# CustomArduino.net
KiCad netlist of a schematic drawn in EAGLE
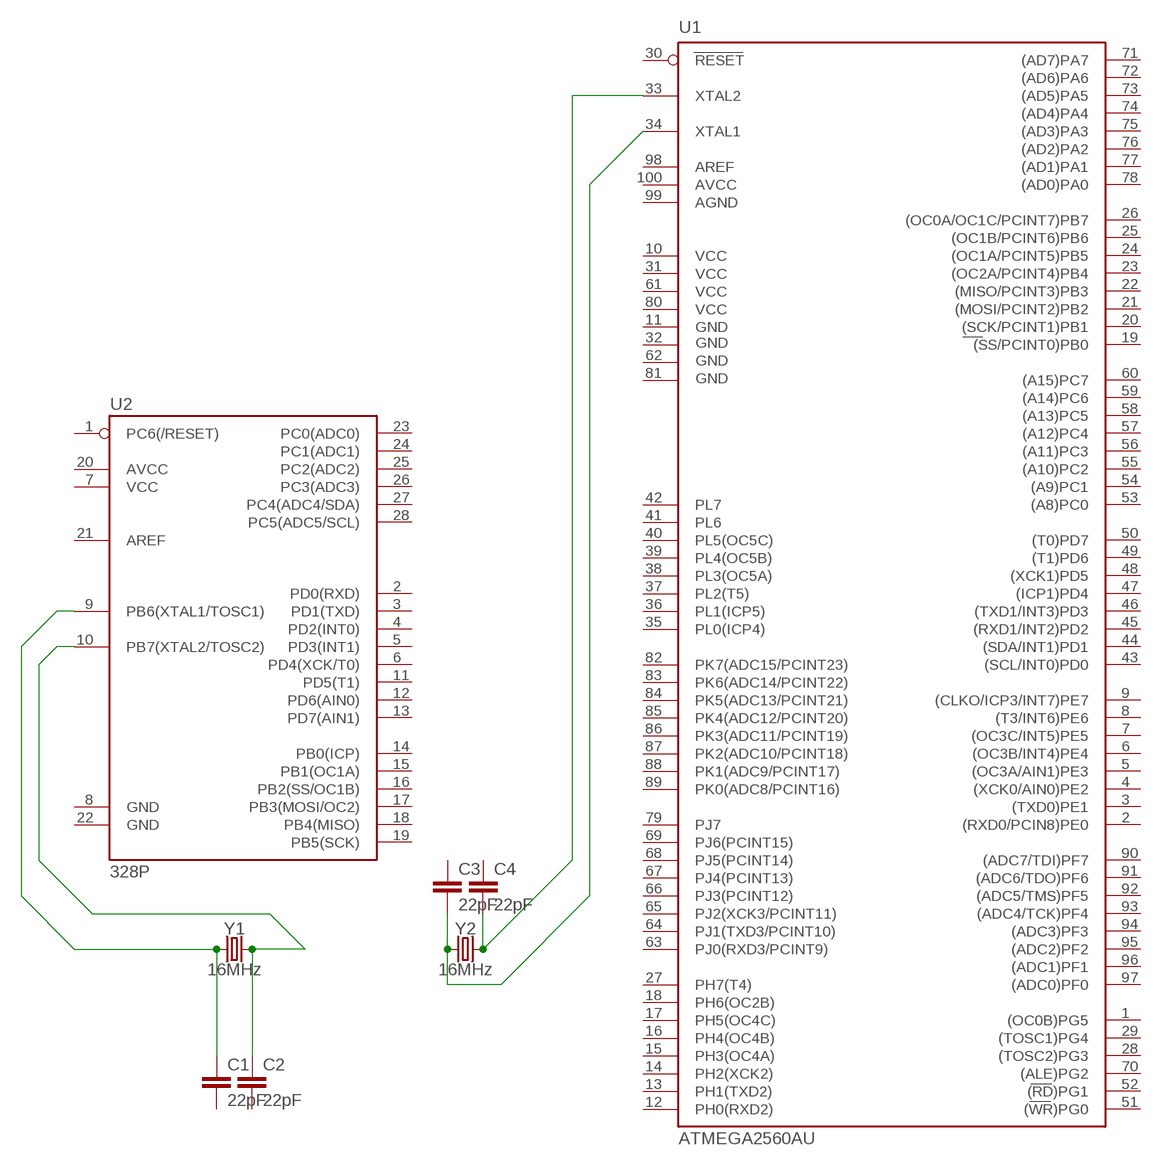
[diagram p0: schematic, sheet 1]

(export (version "E")
  (design (tool "Eeschema 10.0.6"))
  (components
    (comp (ref "C1")
      (value "22pF")
      (footprint "eagle-import:0603")
      (libsource (lib "eagle-import") (part "22PF-0603-50V-5%"))
    )
    (comp (ref "C2")
      (value "22pF")
      (footprint "eagle-import:0603")
      (libsource (lib "eagle-import") (part "22PF-0603-50V-5%"))
    )
    (comp (ref "C3")
      (value "22pF")
      (footprint "eagle-import:0603")
      (libsource (lib "eagle-import") (part "22PF-0603-50V-5%"))
    )
    (comp (ref "C4")
      (value "22pF")
      (footprint "eagle-import:0603")
      (libsource (lib "eagle-import") (part "22PF-0603-50V-5%"))
    )
    (comp (ref "U1")
      (value "ATMEGA2560AU")
      (footprint "eagle-import:TQFP100")
      (libsource (lib "eagle-import") (part "ATMEGA2560AU"))
    )
    (comp (ref "U2")
      (value "328P")
      (footprint "eagle-import:DIP28")
      (libsource (lib "eagle-import") (part "ATMEGA328P_PDIP"))
    )
    (comp (ref "Y1")
      (value "16MHz")
      (footprint "eagle-import:CRYSTAL-SMD-5X3.2-4PAD")
      (libsource (lib "eagle-import") (part "CRYSTAL-16MHZSMD-5X3.2"))
    )
    (comp (ref "Y2")
      (value "16MHz")
      (footprint "eagle-import:CRYSTAL-SMD-5X3.2-4PAD")
      (libsource (lib "eagle-import") (part "CRYSTAL-16MHZSMD-5X3.2"))
    )
  )
  (nets
    (net (code "1") (name "/AGND") (class "Default")
      (node (ref "U1") (pin "99") (pinfunction "AGND_99") (pintype "power_in"))
    )
    (net (code "2") (name "/AVCC") (class "Default")
      (node (ref "U1") (pin "100") (pinfunction "AVCC_100") (pintype "power_in"))
    )
    (net (code "3") (name "/GND") (class "Default")
      (node (ref "U1") (pin "11") (pinfunction "GND_11") (pintype "power_in"))
    )
    (net (code "4") (name "/GND1") (class "Default")
      (node (ref "U1") (pin "32") (pinfunction "GND1_32") (pintype "power_in"))
    )
    (net (code "5") (name "/GND2") (class "Default")
      (node (ref "U1") (pin "62") (pinfunction "GND2_62") (pintype "power_in"))
    )
    (net (code "6") (name "/GND3") (class "Default")
      (node (ref "U1") (pin "81") (pinfunction "GND3_81") (pintype "power_in"))
    )
    (net (code "7") (name "/VCC") (class "Default")
      (node (ref "U1") (pin "10") (pinfunction "VCC_10") (pintype "power_in"))
    )
    (net (code "8") (name "/VCC1") (class "Default")
      (node (ref "U1") (pin "31") (pinfunction "VCC1_31") (pintype "power_in"))
    )
    (net (code "9") (name "/VCC2") (class "Default")
      (node (ref "U1") (pin "61") (pinfunction "VCC2_61") (pintype "power_in"))
    )
    (net (code "10") (name "/VCC3") (class "Default")
      (node (ref "U1") (pin "80") (pinfunction "VCC3_80") (pintype "power_in"))
    )
    (net (code "11") (name "Net-(U1-XTAL1)") (class "Default")
      (node (ref "C3") (pin "2") (pinfunction "2_2") (pintype "passive"))
      (node (ref "U1") (pin "34") (pinfunction "XTAL1_34") (pintype "input"))
      (node (ref "Y2") (pin "1") (pinfunction "1_1") (pintype "passive"))
    )
    (net (code "12") (name "Net-(U1-XTAL2)") (class "Default")
      (node (ref "C4") (pin "2") (pinfunction "2_2") (pintype "passive"))
      (node (ref "U1") (pin "33") (pinfunction "XTAL2_33") (pintype "output"))
      (node (ref "Y2") (pin "3") (pinfunction "2_3") (pintype "passive"))
    )
    (net (code "13") (name "Net-(U2-PB6(XTAL1{slash}TOSC1))") (class "Default")
      (node (ref "C1") (pin "1") (pinfunction "1_1") (pintype "passive"))
      (node (ref "U2") (pin "9") (pinfunction "PB6(XTAL1/TOSC1)_9") (pintype "bidirectional"))
      (node (ref "Y1") (pin "1") (pinfunction "1_1") (pintype "passive"))
    )
    (net (code "14") (name "Net-(U2-PB7(XTAL2{slash}TOSC2))") (class "Default")
      (node (ref "C2") (pin "1") (pinfunction "1_1") (pintype "passive"))
      (node (ref "U2") (pin "10") (pinfunction "PB7(XTAL2/TOSC2)_10") (pintype "bidirectional"))
      (node (ref "Y1") (pin "3") (pinfunction "2_3") (pintype "passive"))
    )
    (net (code "15") (name "unconnected-(C1-Pad2)") (class "Default")
      (node (ref "C1") (pin "2") (pinfunction "2_2") (pintype "passive"))
    )
    (net (code "16") (name "unconnected-(C2-Pad2)") (class "Default")
      (node (ref "C2") (pin "2") (pinfunction "2_2") (pintype "passive"))
    )
    (net (code "17") (name "unconnected-(C3-Pad1)") (class "Default")
      (node (ref "C3") (pin "1") (pinfunction "1_1") (pintype "passive"))
    )
    (net (code "18") (name "unconnected-(C4-Pad1)") (class "Default")
      (node (ref "C4") (pin "1") (pinfunction "1_1") (pintype "passive"))
    )
    (net (code "19") (name "unconnected-(U1-(A8)PC0-Pad53)") (class "Default")
      (node (ref "U1") (pin "53") (pinfunction "(A8)PC0_53") (pintype "bidirectional"))
    )
    (net (code "20") (name "unconnected-(U1-(A9)PC1-Pad54)") (class "Default")
      (node (ref "U1") (pin "54") (pinfunction "(A9)PC1_54") (pintype "bidirectional"))
    )
    (net (code "21") (name "unconnected-(U1-(A10)PC2-Pad55)") (class "Default")
      (node (ref "U1") (pin "55") (pinfunction "(A10)PC2_55") (pintype "bidirectional"))
    )
    (net (code "22") (name "unconnected-(U1-(A11)PC3-Pad56)") (class "Default")
      (node (ref "U1") (pin "56") (pinfunction "(A11)PC3_56") (pintype "bidirectional"))
    )
    (net (code "23") (name "unconnected-(U1-(A12)PC4-Pad57)") (class "Default")
      (node (ref "U1") (pin "57") (pinfunction "(A12)PC4_57") (pintype "bidirectional"))
    )
    (net (code "24") (name "unconnected-(U1-(A13)PC5-Pad58)") (class "Default")
      (node (ref "U1") (pin "58") (pinfunction "(A13)PC5_58") (pintype "bidirectional"))
    )
    (net (code "25") (name "unconnected-(U1-(A14)PC6-Pad59)") (class "Default")
      (node (ref "U1") (pin "59") (pinfunction "(A14)PC6_59") (pintype "bidirectional"))
    )
    (net (code "26") (name "unconnected-(U1-(A15)PC7-Pad60)") (class "Default")
      (node (ref "U1") (pin "60") (pinfunction "(A15)PC7_60") (pintype "bidirectional"))
    )
    (net (code "27") (name "unconnected-(U1-(AD0)PA0-Pad78)") (class "Default")
      (node (ref "U1") (pin "78") (pinfunction "(AD0)PA0_78") (pintype "bidirectional"))
    )
    (net (code "28") (name "unconnected-(U1-(AD1)PA1-Pad77)") (class "Default")
      (node (ref "U1") (pin "77") (pinfunction "(AD1)PA1_77") (pintype "bidirectional"))
    )
    (net (code "29") (name "unconnected-(U1-(AD2)PA2-Pad76)") (class "Default")
      (node (ref "U1") (pin "76") (pinfunction "(AD2)PA2_76") (pintype "bidirectional"))
    )
    (net (code "30") (name "unconnected-(U1-(AD3)PA3-Pad75)") (class "Default")
      (node (ref "U1") (pin "75") (pinfunction "(AD3)PA3_75") (pintype "bidirectional"))
    )
    (net (code "31") (name "unconnected-(U1-(AD4)PA4-Pad74)") (class "Default")
      (node (ref "U1") (pin "74") (pinfunction "(AD4)PA4_74") (pintype "bidirectional"))
    )
    (net (code "32") (name "unconnected-(U1-(AD5)PA5-Pad73)") (class "Default")
      (node (ref "U1") (pin "73") (pinfunction "(AD5)PA5_73") (pintype "bidirectional"))
    )
    (net (code "33") (name "unconnected-(U1-(AD6)PA6-Pad72)") (class "Default")
      (node (ref "U1") (pin "72") (pinfunction "(AD6)PA6_72") (pintype "bidirectional"))
    )
    (net (code "34") (name "unconnected-(U1-(AD7)PA7-Pad71)") (class "Default")
      (node (ref "U1") (pin "71") (pinfunction "(AD7)PA7_71") (pintype "bidirectional"))
    )
    (net (code "35") (name "unconnected-(U1-(ADC0)PF0-Pad97)") (class "Default")
      (node (ref "U1") (pin "97") (pinfunction "(ADC0)PF0_97") (pintype "bidirectional"))
    )
    (net (code "36") (name "unconnected-(U1-(ADC1)PF1-Pad96)") (class "Default")
      (node (ref "U1") (pin "96") (pinfunction "(ADC1)PF1_96") (pintype "bidirectional"))
    )
    (net (code "37") (name "unconnected-(U1-(ADC2)PF2-Pad95)") (class "Default")
      (node (ref "U1") (pin "95") (pinfunction "(ADC2)PF2_95") (pintype "bidirectional"))
    )
    (net (code "38") (name "unconnected-(U1-(ADC3)PF3-Pad94)") (class "Default")
      (node (ref "U1") (pin "94") (pinfunction "(ADC3)PF3_94") (pintype "bidirectional"))
    )
    (net (code "39") (name "unconnected-(U1-(ADC4{slash}TCK)PF4-Pad93)") (class "Default")
      (node (ref "U1") (pin "93") (pinfunction "(ADC4/TCK)PF4_93") (pintype "bidirectional"))
    )
    (net (code "40") (name "unconnected-(U1-(ADC5{slash}TMS)PF5-Pad92)") (class "Default")
      (node (ref "U1") (pin "92") (pinfunction "(ADC5/TMS)PF5_92") (pintype "bidirectional"))
    )
    (net (code "41") (name "unconnected-(U1-(ADC6{slash}TDO)PF6-Pad91)") (class "Default")
      (node (ref "U1") (pin "91") (pinfunction "(ADC6/TDO)PF6_91") (pintype "bidirectional"))
    )
    (net (code "42") (name "unconnected-(U1-(ADC7{slash}TDI)PF7-Pad90)") (class "Default")
      (node (ref "U1") (pin "90") (pinfunction "(ADC7/TDI)PF7_90") (pintype "bidirectional"))
    )
    (net (code "43") (name "unconnected-(U1-(ALE)PG2-Pad70)") (class "Default")
      (node (ref "U1") (pin "70") (pinfunction "(ALE)PG2_70") (pintype "bidirectional"))
    )
    (net (code "44") (name "unconnected-(U1-(CLKO{slash}ICP3{slash}INT7)PE7-Pad9)") (class "Default")
      (node (ref "U1") (pin "9") (pinfunction "(CLKO/ICP3/INT7)PE7_9") (pintype "bidirectional"))
    )
    (net (code "45") (name "unconnected-(U1-(ICP1)PD4-Pad47)") (class "Default")
      (node (ref "U1") (pin "47") (pinfunction "(ICP1)PD4_47") (pintype "bidirectional"))
    )
    (net (code "46") (name "unconnected-(U1-(MISO{slash}PCINT3)PB3-Pad22)") (class "Default")
      (node (ref "U1") (pin "22") (pinfunction "(MISO/PCINT3)PB3_22") (pintype "bidirectional"))
    )
    (net (code "47") (name "unconnected-(U1-(MOSI{slash}PCINT2)PB2-Pad21)") (class "Default")
      (node (ref "U1") (pin "21") (pinfunction "(MOSI/PCINT2)PB2_21") (pintype "bidirectional"))
    )
    (net (code "48") (name "unconnected-(U1-(OC0A{slash}OC1C{slash}PCINT7)PB7-Pad26)") (class "Default")
      (node (ref "U1") (pin "26") (pinfunction "(OC0A/OC1C/PCINT7)PB7_26") (pintype "bidirectional"))
    )
    (net (code "49") (name "unconnected-(U1-(OC0B)PG5-Pad1)") (class "Default")
      (node (ref "U1") (pin "1") (pinfunction "(OC0B)PG5_1") (pintype "bidirectional"))
    )
    (net (code "50") (name "unconnected-(U1-(OC1A{slash}PCINT5)PB5-Pad24)") (class "Default")
      (node (ref "U1") (pin "24") (pinfunction "(OC1A/PCINT5)PB5_24") (pintype "bidirectional"))
    )
    (net (code "51") (name "unconnected-(U1-(OC1B{slash}PCINT6)PB6-Pad25)") (class "Default")
      (node (ref "U1") (pin "25") (pinfunction "(OC1B/PCINT6)PB6_25") (pintype "bidirectional"))
    )
    (net (code "52") (name "unconnected-(U1-(OC2A{slash}PCINT4)PB4-Pad23)") (class "Default")
      (node (ref "U1") (pin "23") (pinfunction "(OC2A/PCINT4)PB4_23") (pintype "bidirectional"))
    )
    (net (code "53") (name "unconnected-(U1-(OC3A{slash}AIN1)PE3-Pad5)") (class "Default")
      (node (ref "U1") (pin "5") (pinfunction "(OC3A/AIN1)PE3_5") (pintype "bidirectional"))
    )
    (net (code "54") (name "unconnected-(U1-(OC3B{slash}INT4)PE4-Pad6)") (class "Default")
      (node (ref "U1") (pin "6") (pinfunction "(OC3B/INT4)PE4_6") (pintype "bidirectional"))
    )
    (net (code "55") (name "unconnected-(U1-(OC3C{slash}INT5)PE5-Pad7)") (class "Default")
      (node (ref "U1") (pin "7") (pinfunction "(OC3C/INT5)PE5_7") (pintype "bidirectional"))
    )
    (net (code "56") (name "unconnected-(U1-(RD)PG1-Pad52)") (class "Default")
      (node (ref "U1") (pin "52") (pinfunction "(RD)PG1_52") (pintype "bidirectional"))
    )
    (net (code "57") (name "unconnected-(U1-(RXD0{slash}PCIN8)PE0-Pad2)") (class "Default")
      (node (ref "U1") (pin "2") (pinfunction "(RXD0/PCIN8)PE0_2") (pintype "bidirectional"))
    )
    (net (code "58") (name "unconnected-(U1-(RXD1{slash}INT2)PD2-Pad45)") (class "Default")
      (node (ref "U1") (pin "45") (pinfunction "(RXD1/INT2)PD2_45") (pintype "bidirectional"))
    )
    (net (code "59") (name "unconnected-(U1-(SCK{slash}PCINT1)PB1-Pad20)") (class "Default")
      (node (ref "U1") (pin "20") (pinfunction "(SCK/PCINT1)PB1_20") (pintype "bidirectional"))
    )
    (net (code "60") (name "unconnected-(U1-(SCL{slash}INT0)PD0-Pad43)") (class "Default")
      (node (ref "U1") (pin "43") (pinfunction "(SCL/INT0)PD0_43") (pintype "bidirectional"))
    )
    (net (code "61") (name "unconnected-(U1-(SDA{slash}INT1)PD1-Pad44)") (class "Default")
      (node (ref "U1") (pin "44") (pinfunction "(SDA/INT1)PD1_44") (pintype "bidirectional"))
    )
    (net (code "62") (name "unconnected-(U1-(SS{slash}PCINT0)PB0-Pad19)") (class "Default")
      (node (ref "U1") (pin "19") (pinfunction "(SS/PCINT0)PB0_19") (pintype "bidirectional"))
    )
    (net (code "63") (name "unconnected-(U1-(T0)PD7-Pad50)") (class "Default")
      (node (ref "U1") (pin "50") (pinfunction "(T0)PD7_50") (pintype "bidirectional"))
    )
    (net (code "64") (name "unconnected-(U1-(T1)PD6-Pad49)") (class "Default")
      (node (ref "U1") (pin "49") (pinfunction "(T1)PD6_49") (pintype "bidirectional"))
    )
    (net (code "65") (name "unconnected-(U1-(T3{slash}INT6)PE6-Pad8)") (class "Default")
      (node (ref "U1") (pin "8") (pinfunction "(T3/INT6)PE6_8") (pintype "bidirectional"))
    )
    (net (code "66") (name "unconnected-(U1-(TOSC1)PG4-Pad29)") (class "Default")
      (node (ref "U1") (pin "29") (pinfunction "(TOSC1)PG4_29") (pintype "bidirectional"))
    )
    (net (code "67") (name "unconnected-(U1-(TOSC2)PG3-Pad28)") (class "Default")
      (node (ref "U1") (pin "28") (pinfunction "(TOSC2)PG3_28") (pintype "bidirectional"))
    )
    (net (code "68") (name "unconnected-(U1-(TXD0)PE1-Pad3)") (class "Default")
      (node (ref "U1") (pin "3") (pinfunction "(TXD0)PE1_3") (pintype "bidirectional"))
    )
    (net (code "69") (name "unconnected-(U1-(TXD1{slash}INT3)PD3-Pad46)") (class "Default")
      (node (ref "U1") (pin "46") (pinfunction "(TXD1/INT3)PD3_46") (pintype "bidirectional"))
    )
    (net (code "70") (name "unconnected-(U1-(WR)PG0-Pad51)") (class "Default")
      (node (ref "U1") (pin "51") (pinfunction "(WR)PG0_51") (pintype "bidirectional"))
    )
    (net (code "71") (name "unconnected-(U1-(XCK0{slash}AIN0)PE2-Pad4)") (class "Default")
      (node (ref "U1") (pin "4") (pinfunction "(XCK0/AIN0)PE2_4") (pintype "bidirectional"))
    )
    (net (code "72") (name "unconnected-(U1-(XCK1)PD5-Pad48)") (class "Default")
      (node (ref "U1") (pin "48") (pinfunction "(XCK1)PD5_48") (pintype "bidirectional"))
    )
    (net (code "73") (name "unconnected-(U1-AREF-Pad98)") (class "Default")
      (node (ref "U1") (pin "98") (pinfunction "AREF_98") (pintype "bidirectional"))
    )
    (net (code "74") (name "unconnected-(U1-PH0(RXD2)-Pad12)") (class "Default")
      (node (ref "U1") (pin "12") (pinfunction "PH0(RXD2)_12") (pintype "bidirectional"))
    )
    (net (code "75") (name "unconnected-(U1-PH1(TXD2)-Pad13)") (class "Default")
      (node (ref "U1") (pin "13") (pinfunction "PH1(TXD2)_13") (pintype "bidirectional"))
    )
    (net (code "76") (name "unconnected-(U1-PH2(XCK2)-Pad14)") (class "Default")
      (node (ref "U1") (pin "14") (pinfunction "PH2(XCK2)_14") (pintype "bidirectional"))
    )
    (net (code "77") (name "unconnected-(U1-PH3(OC4A)-Pad15)") (class "Default")
      (node (ref "U1") (pin "15") (pinfunction "PH3(OC4A)_15") (pintype "bidirectional"))
    )
    (net (code "78") (name "unconnected-(U1-PH4(OC4B)-Pad16)") (class "Default")
      (node (ref "U1") (pin "16") (pinfunction "PH4(OC4B)_16") (pintype "bidirectional"))
    )
    (net (code "79") (name "unconnected-(U1-PH5(OC4C)-Pad17)") (class "Default")
      (node (ref "U1") (pin "17") (pinfunction "PH5(OC4C)_17") (pintype "bidirectional"))
    )
    (net (code "80") (name "unconnected-(U1-PH6(OC2B)-Pad18)") (class "Default")
      (node (ref "U1") (pin "18") (pinfunction "PH6(OC2B)_18") (pintype "bidirectional"))
    )
    (net (code "81") (name "unconnected-(U1-PH7(T4)-Pad27)") (class "Default")
      (node (ref "U1") (pin "27") (pinfunction "PH7(T4)_27") (pintype "bidirectional"))
    )
    (net (code "82") (name "unconnected-(U1-PJ0(RXD3{slash}PCINT9)-Pad63)") (class "Default")
      (node (ref "U1") (pin "63") (pinfunction "PJ0(RXD3/PCINT9)_63") (pintype "bidirectional"))
    )
    (net (code "83") (name "unconnected-(U1-PJ1(TXD3{slash}PCINT10)-Pad64)") (class "Default")
      (node (ref "U1") (pin "64") (pinfunction "PJ1(TXD3/PCINT10)_64") (pintype "bidirectional"))
    )
    (net (code "84") (name "unconnected-(U1-PJ2(XCK3{slash}PCINT11)-Pad65)") (class "Default")
      (node (ref "U1") (pin "65") (pinfunction "PJ2(XCK3/PCINT11)_65") (pintype "bidirectional"))
    )
    (net (code "85") (name "unconnected-(U1-PJ3(PCINT12)-Pad66)") (class "Default")
      (node (ref "U1") (pin "66") (pinfunction "PJ3(PCINT12)_66") (pintype "bidirectional"))
    )
    (net (code "86") (name "unconnected-(U1-PJ4(PCINT13)-Pad67)") (class "Default")
      (node (ref "U1") (pin "67") (pinfunction "PJ4(PCINT13)_67") (pintype "bidirectional"))
    )
    (net (code "87") (name "unconnected-(U1-PJ5(PCINT14)-Pad68)") (class "Default")
      (node (ref "U1") (pin "68") (pinfunction "PJ5(PCINT14)_68") (pintype "bidirectional"))
    )
    (net (code "88") (name "unconnected-(U1-PJ6(PCINT15)-Pad69)") (class "Default")
      (node (ref "U1") (pin "69") (pinfunction "PJ6(PCINT15)_69") (pintype "bidirectional"))
    )
    (net (code "89") (name "unconnected-(U1-PJ7-Pad79)") (class "Default")
      (node (ref "U1") (pin "79") (pinfunction "PJ7_79") (pintype "bidirectional"))
    )
    (net (code "90") (name "unconnected-(U1-PK0(ADC8{slash}PCINT16)-Pad89)") (class "Default")
      (node (ref "U1") (pin "89") (pinfunction "PK0(ADC8/PCINT16)_89") (pintype "bidirectional"))
    )
    (net (code "91") (name "unconnected-(U1-PK1(ADC9{slash}PCINT17)-Pad88)") (class "Default")
      (node (ref "U1") (pin "88") (pinfunction "PK1(ADC9/PCINT17)_88") (pintype "bidirectional"))
    )
    (net (code "92") (name "unconnected-(U1-PK2(ADC10{slash}PCINT18)-Pad87)") (class "Default")
      (node (ref "U1") (pin "87") (pinfunction "PK2(ADC10/PCINT18)_87") (pintype "bidirectional"))
    )
    (net (code "93") (name "unconnected-(U1-PK3(ADC11{slash}PCINT19)-Pad86)") (class "Default")
      (node (ref "U1") (pin "86") (pinfunction "PK3(ADC11/PCINT19)_86") (pintype "bidirectional"))
    )
    (net (code "94") (name "unconnected-(U1-PK4(ADC12{slash}PCINT20)-Pad85)") (class "Default")
      (node (ref "U1") (pin "85") (pinfunction "PK4(ADC12/PCINT20)_85") (pintype "bidirectional"))
    )
    (net (code "95") (name "unconnected-(U1-PK5(ADC13{slash}PCINT21)-Pad84)") (class "Default")
      (node (ref "U1") (pin "84") (pinfunction "PK5(ADC13/PCINT21)_84") (pintype "bidirectional"))
    )
    (net (code "96") (name "unconnected-(U1-PK6(ADC14{slash}PCINT22)-Pad83)") (class "Default")
      (node (ref "U1") (pin "83") (pinfunction "PK6(ADC14/PCINT22)_83") (pintype "bidirectional"))
    )
    (net (code "97") (name "unconnected-(U1-PK7(ADC15{slash}PCINT23)-Pad82)") (class "Default")
      (node (ref "U1") (pin "82") (pinfunction "PK7(ADC15/PCINT23)_82") (pintype "bidirectional"))
    )
    (net (code "98") (name "unconnected-(U1-PL0(ICP4)-Pad35)") (class "Default")
      (node (ref "U1") (pin "35") (pinfunction "PL0(ICP4)_35") (pintype "bidirectional"))
    )
    (net (code "99") (name "unconnected-(U1-PL1(ICP5)-Pad36)") (class "Default")
      (node (ref "U1") (pin "36") (pinfunction "PL1(ICP5)_36") (pintype "bidirectional"))
    )
    (net (code "100") (name "unconnected-(U1-PL2(T5)-Pad37)") (class "Default")
      (node (ref "U1") (pin "37") (pinfunction "PL2(T5)_37") (pintype "bidirectional"))
    )
    (net (code "101") (name "unconnected-(U1-PL3(OC5A)-Pad38)") (class "Default")
      (node (ref "U1") (pin "38") (pinfunction "PL3(OC5A)_38") (pintype "bidirectional"))
    )
    (net (code "102") (name "unconnected-(U1-PL4(OC5B)-Pad39)") (class "Default")
      (node (ref "U1") (pin "39") (pinfunction "PL4(OC5B)_39") (pintype "bidirectional"))
    )
    (net (code "103") (name "unconnected-(U1-PL5(OC5C)-Pad40)") (class "Default")
      (node (ref "U1") (pin "40") (pinfunction "PL5(OC5C)_40") (pintype "bidirectional"))
    )
    (net (code "104") (name "unconnected-(U1-PL6-Pad41)") (class "Default")
      (node (ref "U1") (pin "41") (pinfunction "PL6_41") (pintype "bidirectional"))
    )
    (net (code "105") (name "unconnected-(U1-PL7-Pad42)") (class "Default")
      (node (ref "U1") (pin "42") (pinfunction "PL7_42") (pintype "bidirectional"))
    )
    (net (code "106") (name "unconnected-(U1-RESET-Pad30)") (class "Default")
      (node (ref "U1") (pin "30") (pinfunction "RESET_30") (pintype "input"))
    )
    (net (code "107") (name "unconnected-(U2-AREF-Pad21)") (class "Default")
      (node (ref "U2") (pin "21") (pinfunction "AREF_21") (pintype "bidirectional"))
    )
    (net (code "108") (name "unconnected-(U2-AVCC-Pad20)") (class "Default")
      (node (ref "U2") (pin "20") (pinfunction "AVCC_20") (pintype "bidirectional"))
    )
    (net (code "109") (name "unconnected-(U2-GND-Pad8)") (class "Default")
      (node (ref "U2") (pin "8") (pinfunction "GND_8") (pintype "bidirectional"))
    )
    (net (code "110") (name "unconnected-(U2-GND-Pad22)") (class "Default")
      (node (ref "U2") (pin "22") (pinfunction "GND_22") (pintype "bidirectional"))
    )
    (net (code "111") (name "unconnected-(U2-PB0(ICP)-Pad14)") (class "Default")
      (node (ref "U2") (pin "14") (pinfunction "PB0(ICP)_14") (pintype "bidirectional"))
    )
    (net (code "112") (name "unconnected-(U2-PB1(OC1A)-Pad15)") (class "Default")
      (node (ref "U2") (pin "15") (pinfunction "PB1(OC1A)_15") (pintype "bidirectional"))
    )
    (net (code "113") (name "unconnected-(U2-PB2(SS{slash}OC1B)-Pad16)") (class "Default")
      (node (ref "U2") (pin "16") (pinfunction "PB2(SS/OC1B)_16") (pintype "bidirectional"))
    )
    (net (code "114") (name "unconnected-(U2-PB3(MOSI{slash}OC2)-Pad17)") (class "Default")
      (node (ref "U2") (pin "17") (pinfunction "PB3(MOSI/OC2)_17") (pintype "bidirectional"))
    )
    (net (code "115") (name "unconnected-(U2-PB4(MISO)-Pad18)") (class "Default")
      (node (ref "U2") (pin "18") (pinfunction "PB4(MISO)_18") (pintype "bidirectional"))
    )
    (net (code "116") (name "unconnected-(U2-PB5(SCK)-Pad19)") (class "Default")
      (node (ref "U2") (pin "19") (pinfunction "PB5(SCK)_19") (pintype "bidirectional"))
    )
    (net (code "117") (name "unconnected-(U2-PC0(ADC0)-Pad23)") (class "Default")
      (node (ref "U2") (pin "23") (pinfunction "PC0(ADC0)_23") (pintype "bidirectional"))
    )
    (net (code "118") (name "unconnected-(U2-PC1(ADC1)-Pad24)") (class "Default")
      (node (ref "U2") (pin "24") (pinfunction "PC1(ADC1)_24") (pintype "bidirectional"))
    )
    (net (code "119") (name "unconnected-(U2-PC2(ADC2)-Pad25)") (class "Default")
      (node (ref "U2") (pin "25") (pinfunction "PC2(ADC2)_25") (pintype "bidirectional"))
    )
    (net (code "120") (name "unconnected-(U2-PC3(ADC3)-Pad26)") (class "Default")
      (node (ref "U2") (pin "26") (pinfunction "PC3(ADC3)_26") (pintype "bidirectional"))
    )
    (net (code "121") (name "unconnected-(U2-PC4(ADC4{slash}SDA)-Pad27)") (class "Default")
      (node (ref "U2") (pin "27") (pinfunction "PC4(ADC4/SDA)_27") (pintype "bidirectional"))
    )
    (net (code "122") (name "unconnected-(U2-PC5(ADC5{slash}SCL)-Pad28)") (class "Default")
      (node (ref "U2") (pin "28") (pinfunction "PC5(ADC5/SCL)_28") (pintype "bidirectional"))
    )
    (net (code "123") (name "unconnected-(U2-PC6({slash}RESET)-Pad1)") (class "Default")
      (node (ref "U2") (pin "1") (pinfunction "PC6(/RESET)_1") (pintype "bidirectional"))
    )
    (net (code "124") (name "unconnected-(U2-PD0(RXD)-Pad2)") (class "Default")
      (node (ref "U2") (pin "2") (pinfunction "PD0(RXD)_2") (pintype "bidirectional"))
    )
    (net (code "125") (name "unconnected-(U2-PD1(TXD)-Pad3)") (class "Default")
      (node (ref "U2") (pin "3") (pinfunction "PD1(TXD)_3") (pintype "bidirectional"))
    )
    (net (code "126") (name "unconnected-(U2-PD2(INT0)-Pad4)") (class "Default")
      (node (ref "U2") (pin "4") (pinfunction "PD2(INT0)_4") (pintype "bidirectional"))
    )
    (net (code "127") (name "unconnected-(U2-PD3(INT1)-Pad5)") (class "Default")
      (node (ref "U2") (pin "5") (pinfunction "PD3(INT1)_5") (pintype "bidirectional"))
    )
    (net (code "128") (name "unconnected-(U2-PD4(XCK{slash}T0)-Pad6)") (class "Default")
      (node (ref "U2") (pin "6") (pinfunction "PD4(XCK/T0)_6") (pintype "bidirectional"))
    )
    (net (code "129") (name "unconnected-(U2-PD5(T1)-Pad11)") (class "Default")
      (node (ref "U2") (pin "11") (pinfunction "PD5(T1)_11") (pintype "bidirectional"))
    )
    (net (code "130") (name "unconnected-(U2-PD6(AIN0)-Pad12)") (class "Default")
      (node (ref "U2") (pin "12") (pinfunction "PD6(AIN0)_12") (pintype "bidirectional"))
    )
    (net (code "131") (name "unconnected-(U2-PD7(AIN1)-Pad13)") (class "Default")
      (node (ref "U2") (pin "13") (pinfunction "PD7(AIN1)_13") (pintype "bidirectional"))
    )
    (net (code "132") (name "unconnected-(U2-VCC-Pad7)") (class "Default")
      (node (ref "U2") (pin "7") (pinfunction "VCC_7") (pintype "bidirectional"))
    )
  )
)
